# pmu.net
KiCad netlist of a schematic drawn in Altium Designer
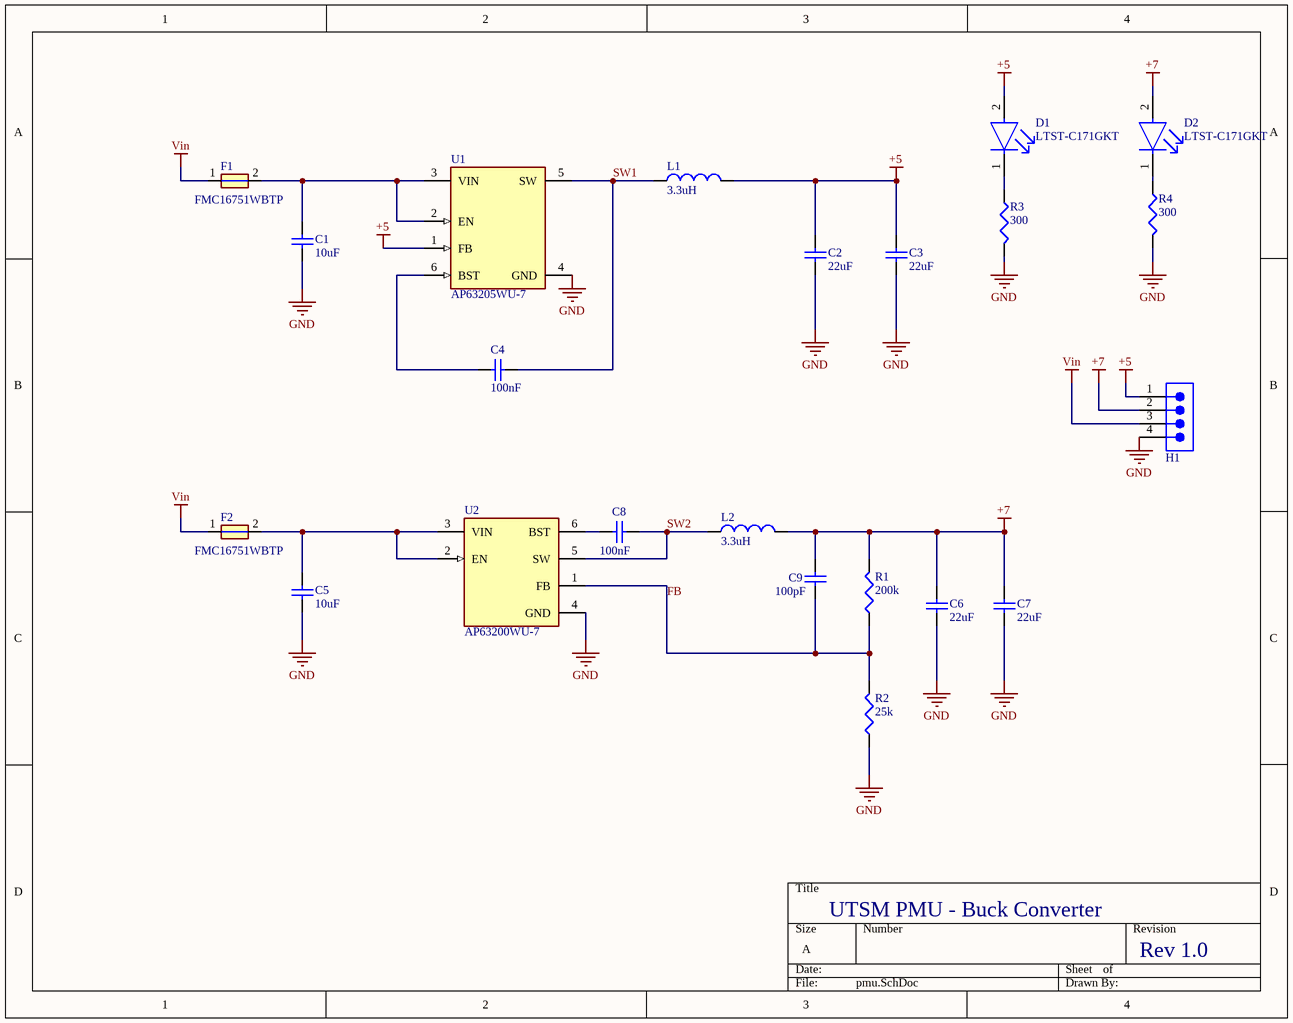
[diagram p0: pmu.SchDoc]

(export (version "E")
  (design (tool "Eeschema 10.0.6"))
  (components
    (comp (ref "C1")
      (value "10uF")
      (footprint "0603c")
      (description "SMD Capacitor\r\nCL21A106KOQNNNG")
      (fields (field (name "Comment") "Cap") (field (name "PUBLISHER") "Altium Limited"))
      (libsource (lib "pmu") (part "Cap"))
    )
    (comp (ref "C2")
      (value "22uF")
      (footprint "0603c")
      (description "SMD Capacitor")
      (fields (field (name "Comment") "Cap") (field (name "PUBLISHER") "Altium Limited"))
      (libsource (lib "pmu") (part "Cap"))
    )
    (comp (ref "C3")
      (value "22uF")
      (footprint "0603c")
      (description "SMD Capacitor")
      (fields (field (name "Comment") "Cap") (field (name "PUBLISHER") "Altium Limited"))
      (libsource (lib "pmu") (part "Cap"))
    )
    (comp (ref "C4")
      (value "100nF")
      (footprint "0603c")
      (description "SMD Capacitor")
      (fields (field (name "Comment") "Cap") (field (name "PUBLISHER") "Altium Limited"))
      (libsource (lib "pmu") (part "Cap"))
    )
    (comp (ref "C5")
      (value "10uF")
      (footprint "0603c")
      (description "SMD Capacitor\r\nCL21A106KOQNNNG")
      (fields (field (name "Comment") "Cap") (field (name "PUBLISHER") "Altium Limited"))
      (libsource (lib "pmu") (part "Cap"))
    )
    (comp (ref "C6")
      (value "22uF")
      (footprint "0603c")
      (description "SMD Capacitor")
      (fields (field (name "Comment") "Cap") (field (name "PUBLISHER") "Altium Limited"))
      (libsource (lib "pmu") (part "Cap"))
    )
    (comp (ref "C7")
      (value "22uF")
      (footprint "0603c")
      (description "SMD Capacitor")
      (fields (field (name "Comment") "Cap") (field (name "PUBLISHER") "Altium Limited"))
      (libsource (lib "pmu") (part "Cap"))
    )
    (comp (ref "C8")
      (value "100nF")
      (footprint "0603c")
      (description "SMD Capacitor")
      (fields (field (name "Comment") "Cap") (field (name "PUBLISHER") "Altium Limited"))
      (libsource (lib "pmu") (part "Cap"))
    )
    (comp (ref "C9")
      (value "100pF")
      (footprint "0603c")
      (description "SMD Capacitor")
      (fields (field (name "Comment") "Cap") (field (name "PUBLISHER") "Altium Limited"))
      (libsource (lib "pmu") (part "Cap"))
    )
    (comp (ref "D1")
      (value "LTST-C171GKT")
      (footprint "FP-LTST-C171GKT-MFG")
      (description "LED GREEN CLEAR CHIP SMD")
      (libsource (lib "Altium Content Vault") (part "8706943c75ba83719d021d2fdc84c58"))
    )
    (comp (ref "D2")
      (value "LTST-C171GKT")
      (footprint "FP-LTST-C171GKT-MFG")
      (description "LED GREEN CLEAR CHIP SMD")
      (libsource (lib "Altium Content Vault") (part "8706943c75ba83719d021d2fdc84c58"))
    )
    (comp (ref "F1")
      (value "FMC16751WBTP")
      (footprint "FUSC1608X64N")
      (description "0.8A - FMC16801WHTP\r\n0.75A - FMC16751WBTP")
      (fields (field (name "MP") "ERB-RE1R00V") (field (name "MF") "Panasonic"))
      (libsource (lib "pmu") (part "ERB-RE1R00V"))
    )
    (comp (ref "F2")
      (value "FMC16751WBTP")
      (footprint "FUSC1608X64N")
      (description "0.8A - FMC16801WHTP\r\n0.75A - FMC16751WBTP")
      (fields (field (name "MP") "ERB-RE1R00V") (field (name "MF") "Panasonic"))
      (libsource (lib "pmu") (part "ERB-RE1R00V"))
    )
    (comp (ref "H1")
      (value "61300411121")
      (footprint "61300411121")
      (description "WR-PHD Pin Header, THT, Vertical, pitch 2.54mm, 1 Row, 4P")
      (fields (field (name "MANUFACTURER") "Wurth Elektronik"))
      (libsource (lib "pmu") (part "61300411121"))
    )
    (comp (ref "L1")
      (value "3.3uH")
      (footprint "1210")
      (description "SMD Inductor\r\nSRP3212-3R3M")
      (fields (field (name "MF") "Bourns") (field (name "MP") "SRP3212-4R7M"))
      (libsource (lib "pmu") (part "Ind"))
    )
    (comp (ref "L2")
      (value "3.3uH")
      (footprint "1210")
      (description "SMD Inductor\r\nSRP3212-3R3M")
      (fields (field (name "MF") "Bourns") (field (name "MP") "SRP3212-4R7M"))
      (libsource (lib "pmu") (part "Ind"))
    )
    (comp (ref "R1")
      (value "200k")
      (footprint "0603r")
      (description "SMD Resistor")
      (fields (field (name "Comment") "Res3") (field (name "PUBLISHER") "Altium Limited"))
      (libsource (lib "pmu") (part "Res3"))
    )
    (comp (ref "R2")
      (value "25k")
      (footprint "0603r")
      (description "SMD Resistor")
      (fields (field (name "Comment") "Res3") (field (name "PUBLISHER") "Altium Limited"))
      (libsource (lib "pmu") (part "Res3"))
    )
    (comp (ref "R3")
      (value "300")
      (footprint "0603r")
      (description "SMD Resistor")
      (fields (field (name "PUBLISHER") "Altium Limited"))
      (libsource (lib "pmu") (part "Res3"))
    )
    (comp (ref "R4")
      (value "300")
      (footprint "0603r")
      (description "SMD Resistor")
      (fields (field (name "PUBLISHER") "Altium Limited"))
      (libsource (lib "pmu") (part "Res3"))
    )
    (comp (ref "U1")
      (value "AP63205WU-7")
      (footprint "FP-TSOT26-MFG")
      (description "IC REG BUCK 5V 2A TSOT26")
      (fields
        (field (name "MANUFACTURER") "Diodes Inc.")
        (field (name "OCTOPART") "https://octopart.com/ap63205wu-7-diodes+inc.-98099551")
      )
      (libsource (lib "Altium Content Vault") (part "029bc9fbfa4a99dbb8b3a24c2adb655"))
    )
    (comp (ref "U2")
      (value "AP63200WU-7")
      (footprint "FP-TSOT26-MFG")
      (description "IC REG BUCK ADJUSTABLE 2A TSOT26")
      (fields
        (field (name "OCTOPART") "https://octopart.com/ap63200wu-7-diodes+inc.-98099548")
        (field (name "MANUFACTURER") "Diodes Inc.")
      )
      (libsource (lib "Altium Content Vault") (part "2ae3aed49e7ee94ca813948749813a1"))
    )
  )
  (nets
    (net (code "1") (name "+5") (class "Default")
      (node (ref "C2") (pin "2") (pinfunction "2_2") (pintype "passive"))
      (node (ref "C3") (pin "2") (pinfunction "2_2") (pintype "passive"))
      (node (ref "D1") (pin "2") (pinfunction "A_2") (pintype "passive"))
      (node (ref "H1") (pin "1") (pinfunction "1_1") (pintype "passive"))
      (node (ref "L1") (pin "P$2") (pinfunction "2_P$2") (pintype "passive"))
      (node (ref "U1") (pin "1") (pinfunction "FB_1") (pintype "input"))
    )
    (net (code "2") (name "+7") (class "Default")
      (node (ref "C6") (pin "2") (pinfunction "2_2") (pintype "passive"))
      (node (ref "C7") (pin "2") (pinfunction "2_2") (pintype "passive"))
      (node (ref "C9") (pin "2") (pinfunction "2_2") (pintype "passive"))
      (node (ref "D2") (pin "2") (pinfunction "A_2") (pintype "passive"))
      (node (ref "H1") (pin "2") (pinfunction "2_2") (pintype "passive"))
      (node (ref "L2") (pin "P$2") (pinfunction "2_P$2") (pintype "passive"))
      (node (ref "R1") (pin "2") (pinfunction "2_2") (pintype "passive"))
    )
    (net (code "3") (name "/FB") (class "Default")
      (node (ref "C9") (pin "1") (pinfunction "1_1") (pintype "passive"))
      (node (ref "R1") (pin "1") (pinfunction "1_1") (pintype "passive"))
      (node (ref "R2") (pin "2") (pinfunction "2_2") (pintype "passive"))
      (node (ref "U2") (pin "1") (pinfunction "FB_1") (pintype "passive"))
    )
    (net (code "4") (name "/SW1") (class "Default")
      (node (ref "C4") (pin "2") (pinfunction "2_2") (pintype "passive"))
      (node (ref "L1") (pin "P$1") (pinfunction "1_P$1") (pintype "passive"))
      (node (ref "U1") (pin "5") (pinfunction "SW_5") (pintype "power_in"))
    )
    (net (code "5") (name "/SW2") (class "Default")
      (node (ref "C8") (pin "2") (pinfunction "2_2") (pintype "passive"))
      (node (ref "L2") (pin "P$1") (pinfunction "1_P$1") (pintype "passive"))
      (node (ref "U2") (pin "5") (pinfunction "SW_5") (pintype "passive"))
    )
    (net (code "6") (name "GND") (class "Default")
      (node (ref "C1") (pin "1") (pinfunction "1_1") (pintype "passive"))
      (node (ref "C2") (pin "1") (pinfunction "1_1") (pintype "passive"))
      (node (ref "C3") (pin "1") (pinfunction "1_1") (pintype "passive"))
      (node (ref "C5") (pin "1") (pinfunction "1_1") (pintype "passive"))
      (node (ref "C6") (pin "1") (pinfunction "1_1") (pintype "passive"))
      (node (ref "C7") (pin "1") (pinfunction "1_1") (pintype "passive"))
      (node (ref "H1") (pin "4") (pinfunction "4_4") (pintype "passive"))
      (node (ref "R2") (pin "1") (pinfunction "1_1") (pintype "passive"))
      (node (ref "R3") (pin "2") (pinfunction "2_2") (pintype "passive"))
      (node (ref "R4") (pin "2") (pinfunction "2_2") (pintype "passive"))
      (node (ref "U1") (pin "4") (pinfunction "GND_4") (pintype "power_in"))
      (node (ref "U2") (pin "4") (pinfunction "GND_4") (pintype "power_in"))
    )
    (net (code "7") (name "Net-(D1-C)") (class "Default")
      (node (ref "D1") (pin "1") (pinfunction "C_1") (pintype "passive"))
      (node (ref "R3") (pin "1") (pinfunction "1_1") (pintype "passive"))
    )
    (net (code "8") (name "Net-(D2-C)") (class "Default")
      (node (ref "D2") (pin "1") (pinfunction "C_1") (pintype "passive"))
      (node (ref "R4") (pin "1") (pinfunction "1_1") (pintype "passive"))
    )
    (net (code "9") (name "Net-(U1-BST)") (class "Default")
      (node (ref "C4") (pin "1") (pinfunction "1_1") (pintype "passive"))
      (node (ref "U1") (pin "6") (pinfunction "BST_6") (pintype "input"))
    )
    (net (code "10") (name "Net-(U1-EN)") (class "Default")
      (node (ref "C1") (pin "2") (pinfunction "2_2") (pintype "passive"))
      (node (ref "F1") (pin "2") (pinfunction "2_2") (pintype "passive"))
      (node (ref "U1") (pin "2") (pinfunction "EN_2") (pintype "input"))
      (node (ref "U1") (pin "3") (pinfunction "VIN_3") (pintype "power_in"))
    )
    (net (code "11") (name "Net-(U2-BST)") (class "Default")
      (node (ref "C8") (pin "1") (pinfunction "1_1") (pintype "passive"))
      (node (ref "U2") (pin "6") (pinfunction "BST_6") (pintype "passive"))
    )
    (net (code "12") (name "Net-(U2-EN)") (class "Default")
      (node (ref "C5") (pin "2") (pinfunction "2_2") (pintype "passive"))
      (node (ref "F2") (pin "2") (pinfunction "2_2") (pintype "passive"))
      (node (ref "U2") (pin "2") (pinfunction "EN_2") (pintype "input"))
      (node (ref "U2") (pin "3") (pinfunction "VIN_3") (pintype "power_in"))
    )
    (net (code "13") (name "Vin") (class "Default")
      (node (ref "F1") (pin "1") (pinfunction "1_1") (pintype "passive"))
      (node (ref "F2") (pin "1") (pinfunction "1_1") (pintype "passive"))
      (node (ref "H1") (pin "3") (pinfunction "3_3") (pintype "passive"))
    )
  )
)
